# RFR24_AMS_Design_-_LTC6820_V1.net
KiCad netlist of a schematic drawn in Altium Designer
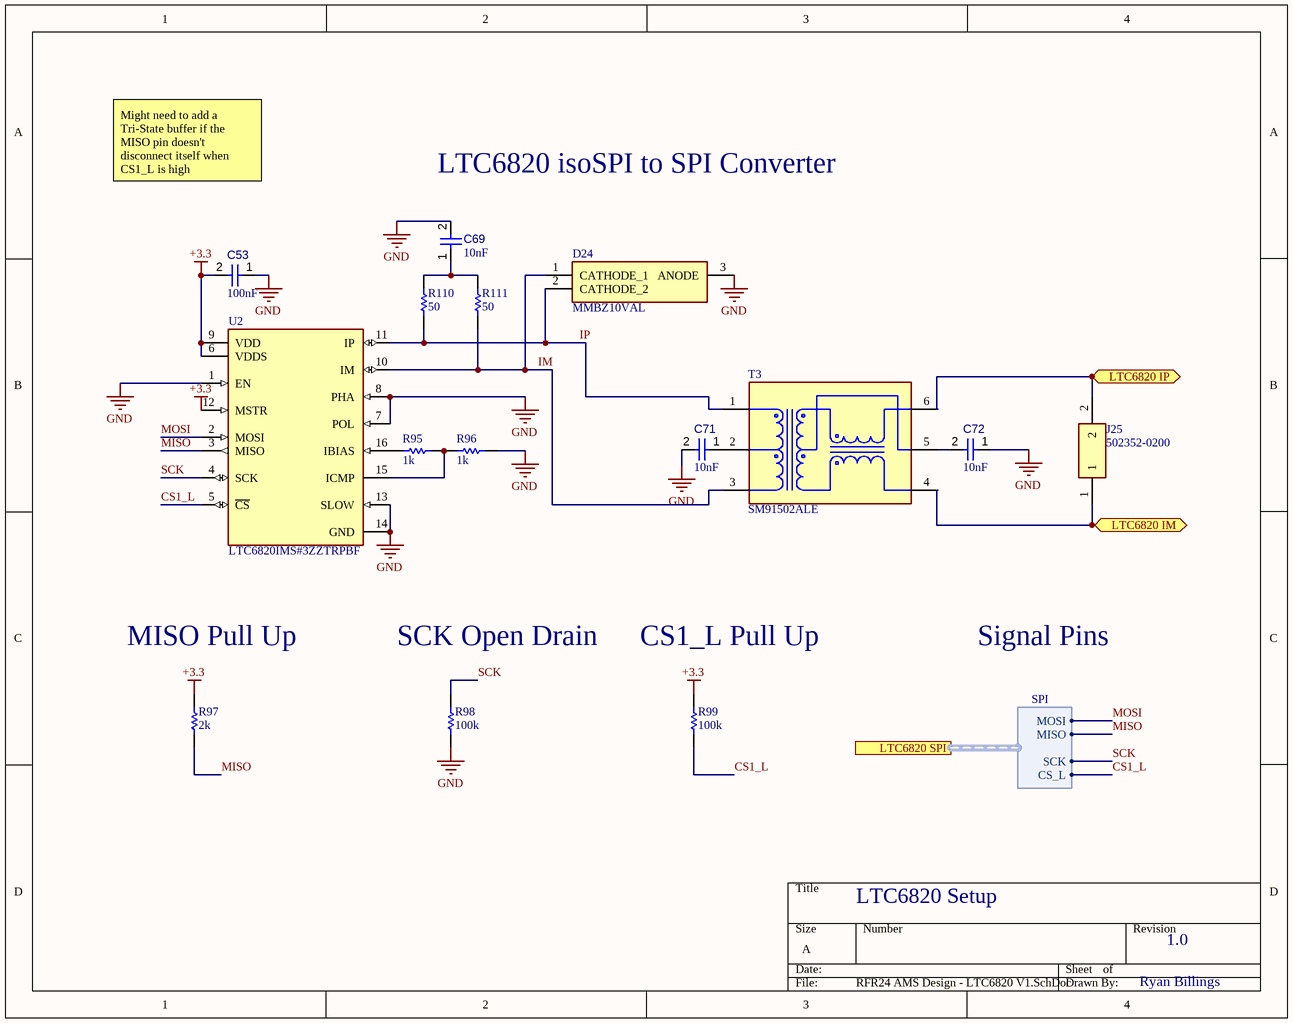
[diagram p0: RFR24 AMS Design - LTC6820 V1.SchDoc]

(export (version "E")
  (design (tool "Eeschema 10.0.6"))
  (components
    (comp (ref "C53")
      (value "100nF")
      (footprint "CAPC2013X145X50LL20T25")
      (description "Chip Capacitor, 1 uF, +/-10%, 25 V, 0805 (2012 Metric)")
      (fields (field (name "TOLERANCE") "10%") (field (name "Comment") "Capacitor 1 uF +/- 10% 25 V 0805"))
      (libsource (lib "Rutgers University") (part "CAP-NP-2"))
    )
    (comp (ref "C69")
      (value "10nF")
      (footprint "CAPC2013X145X50LL20T25")
      (description "Chip Capacitor, 1 uF, +/-10%, 25 V, 0805 (2012 Metric)")
      (fields (field (name "TOLERANCE") "10%") (field (name "Comment") "Capacitor 1 uF +/- 10% 25 V 0805"))
      (libsource (lib "Rutgers University") (part "CAP-NP-2"))
    )
    (comp (ref "C71")
      (value "10nF")
      (footprint "CAPC2013X145X50LL20T25")
      (description "Chip Capacitor, 1 uF, +/-10%, 25 V, 0805 (2012 Metric)")
      (fields (field (name "TOLERANCE") "10%") (field (name "Comment") "Capacitor 1 uF +/- 10% 25 V 0805"))
      (libsource (lib "Rutgers University") (part "CAP-NP-2"))
    )
    (comp (ref "C72")
      (value "10nF")
      (footprint "CAPC2013X145X50LL20T25")
      (description "Chip Capacitor, 1 uF, +/-10%, 25 V, 0805 (2012 Metric)")
      (fields (field (name "TOLERANCE") "10%") (field (name "Comment") "Capacitor 1 uF +/- 10% 25 V 0805"))
      (libsource (lib "Rutgers University") (part "CAP-NP-2"))
    )
    (comp (ref "D24")
      (value "MMBZ10VAL")
      (footprint "SamacSys:SOT95P230X110-3N")
      (description "TVS Diode (Uni-directional)")
      (libsource (lib "*") (part "MMBZ10VAL"))
    )
    (comp (ref "J25")
      (value "502352-0200")
      (footprint "SamacSys:5023520200")
      (description "Connector")
      (fields (field (name "MOUSER PART NUMBER") "538-502352-0200"))
      (libsource (lib "*") (part "502352-0200"))
    )
    (comp (ref "R95")
      (value "1k")
      (footprint "RESC2013X70X40LL20T20")
      (description "Chip Resistor, 1 KOhm, +/- 1%, 0.125 W, -55 to 155 degC, 0805 (2013 Metric)")
      (fields (field (name "TOLERANCE") "1%") (field (name "POWER") "125mW"))
      (libsource (lib "Rutgers University") (part "RES-2"))
    )
    (comp (ref "R96")
      (value "1k")
      (footprint "RESC2013X70X40LL20T20")
      (description "Chip Resistor, 1 KOhm, +/- 1%, 0.125 W, -55 to 155 degC, 0805 (2013 Metric)")
      (fields (field (name "TOLERANCE") "1%") (field (name "POWER") "125mW"))
      (libsource (lib "Rutgers University") (part "RES-2"))
    )
    (comp (ref "R97")
      (value "2k")
      (footprint "RESC2013X70X40LL20T20")
      (description "Chip Resistor, 1 KOhm, +/- 1%, 0.125 W, -55 to 155 degC, 0805 (2013 Metric)")
      (fields (field (name "TOLERANCE") "1%") (field (name "POWER") "125mW"))
      (libsource (lib "Rutgers University") (part "RES-2"))
    )
    (comp (ref "R98")
      (value "100k")
      (footprint "RESC2013X70X40LL20T20")
      (description "Chip Resistor, 1 KOhm, +/- 1%, 0.125 W, -55 to 155 degC, 0805 (2013 Metric)")
      (fields (field (name "TOLERANCE") "1%") (field (name "POWER") "125mW"))
      (libsource (lib "Rutgers University") (part "RES-2"))
    )
    (comp (ref "R99")
      (value "100k")
      (footprint "RESC2013X70X40LL20T20")
      (description "Chip Resistor, 1 KOhm, +/- 1%, 0.125 W, -55 to 155 degC, 0805 (2013 Metric)")
      (fields (field (name "TOLERANCE") "1%") (field (name "POWER") "125mW"))
      (libsource (lib "Rutgers University") (part "RES-2"))
    )
    (comp (ref "R110")
      (value "50")
      (footprint "RESC2013X70X40LL20T20")
      (description "Chip Resistor, 1 KOhm, +/- 1%, 0.125 W, -55 to 155 degC, 0805 (2013 Metric)")
      (fields (field (name "TOLERANCE") "1%") (field (name "POWER") "125mW"))
      (libsource (lib "Rutgers University") (part "RES-2"))
    )
    (comp (ref "R111")
      (value "50")
      (footprint "RESC2013X70X40LL20T20")
      (description "Chip Resistor, 1 KOhm, +/- 1%, 0.125 W, -55 to 155 degC, 0805 (2013 Metric)")
      (fields (field (name "TOLERANCE") "1%") (field (name "POWER") "125mW"))
      (libsource (lib "Rutgers University") (part "RES-2"))
    )
    (comp (ref "T3")
      (value "SM91502ALE")
      (footprint "FP-SM91502ALE-MFG")
      (description "BMS XFORMER 1-CH 1000V AECQ +125")
      (fields
        (field (name "MANUFACTURER") "Bourns")
        (field (name "OCTOPART") "https://octopart.com/sm91502ale-bourns-95732123")
      )
      (libsource (lib "Altium Content Vault") (part "554ff5199021d68917f526d8699f58a"))
    )
    (comp (ref "U2")
      (value "LTC6820IMS#3ZZTRPBF")
      (footprint "FP-MS-16-05-08-1669-IPC_C")
      (description "IC INTERFACE SPECIALIZED 16MSOP")
      (libsource (lib "Altium Content Vault") (part "435d8f2fce35f3197db5f67e0dab696"))
    )
  )
  (nets
    (net (code "2") (name "+3.3") (class "Default")
      (node (ref "C53") (pin "2") (pinfunction "2_2") (pintype "passive"))
      (node (ref "R97") (pin "2") (pinfunction "2_2") (pintype "passive"))
      (node (ref "R99") (pin "2") (pinfunction "2_2") (pintype "passive"))
      (node (ref "U2") (pin "12") (pinfunction "MSTR_12") (pintype "input"))
      (node (ref "U2") (pin "6") (pinfunction "VDDS_6") (pintype "power_in"))
      (node (ref "U2") (pin "9") (pinfunction "VDD_9") (pintype "power_in"))
    )
    (net (code "3") (name "/CS1_L") (class "Default")
      (node (ref "R99") (pin "1") (pinfunction "1_1") (pintype "passive"))
      (node (ref "U2") (pin "5") (pinfunction "~{CS}_5") (pintype "bidirectional"))
    )
    (net (code "4") (name "/IM") (class "Default")
      (node (ref "D24") (pin "1") (pinfunction "CATHODE_1_1") (pintype "passive"))
      (node (ref "R111") (pin "1") (pinfunction "1_1") (pintype "passive"))
      (node (ref "T3") (pin "3") (pinfunction "3_3") (pintype "passive"))
      (node (ref "U2") (pin "10") (pinfunction "IM_10") (pintype "bidirectional"))
    )
    (net (code "5") (name "/IP") (class "Default")
      (node (ref "D24") (pin "2") (pinfunction "CATHODE_2_2") (pintype "passive"))
      (node (ref "R110") (pin "1") (pinfunction "1_1") (pintype "passive"))
      (node (ref "T3") (pin "1") (pinfunction "1_1") (pintype "passive"))
      (node (ref "U2") (pin "11") (pinfunction "IP_11") (pintype "bidirectional"))
    )
    (net (code "6") (name "/LTC6820 IM") (class "Default")
      (node (ref "J25") (pin "1") (pinfunction "1_1") (pintype "passive"))
      (node (ref "T3") (pin "4") (pinfunction "4_4") (pintype "passive"))
    )
    (net (code "7") (name "/LTC6820 IP") (class "Default")
      (node (ref "J25") (pin "2") (pinfunction "2_2") (pintype "passive"))
      (node (ref "T3") (pin "6") (pinfunction "6_6") (pintype "passive"))
    )
    (net (code "8") (name "/MISO") (class "Default")
      (node (ref "R97") (pin "1") (pinfunction "1_1") (pintype "passive"))
      (node (ref "U2") (pin "3") (pinfunction "MISO_3") (pintype "output"))
    )
    (net (code "9") (name "/MOSI") (class "Default")
      (node (ref "U2") (pin "2") (pinfunction "MOSI_2") (pintype "input"))
    )
    (net (code "10") (name "/SCK") (class "Default")
      (node (ref "R98") (pin "2") (pinfunction "2_2") (pintype "passive"))
      (node (ref "U2") (pin "4") (pinfunction "SCK_4") (pintype "bidirectional"))
    )
    (net (code "12") (name "GND") (class "Default")
      (node (ref "C53") (pin "1") (pinfunction "1_1") (pintype "passive"))
      (node (ref "C69") (pin "2") (pinfunction "2_2") (pintype "passive"))
      (node (ref "C71") (pin "2") (pinfunction "2_2") (pintype "passive"))
      (node (ref "C72") (pin "1") (pinfunction "1_1") (pintype "passive"))
      (node (ref "D24") (pin "3") (pinfunction "ANODE_3") (pintype "passive"))
      (node (ref "R96") (pin "2") (pinfunction "2_2") (pintype "passive"))
      (node (ref "R98") (pin "1") (pinfunction "1_1") (pintype "passive"))
      (node (ref "U2") (pin "1") (pinfunction "EN_1") (pintype "input"))
      (node (ref "U2") (pin "13") (pinfunction "SLOW_13") (pintype "input"))
      (node (ref "U2") (pin "14") (pinfunction "GND_14") (pintype "power_in"))
      (node (ref "U2") (pin "7") (pinfunction "POL_7") (pintype "input"))
      (node (ref "U2") (pin "8") (pinfunction "PHA_8") (pintype "input"))
    )
    (net (code "13") (name "Net-(C69-Pad1)") (class "Default")
      (node (ref "C69") (pin "1") (pinfunction "1_1") (pintype "passive"))
      (node (ref "R110") (pin "2") (pinfunction "2_2") (pintype "passive"))
      (node (ref "R111") (pin "2") (pinfunction "2_2") (pintype "passive"))
    )
    (net (code "14") (name "Net-(C71-Pad1)") (class "Default")
      (node (ref "C71") (pin "1") (pinfunction "1_1") (pintype "passive"))
      (node (ref "T3") (pin "2") (pinfunction "2_2") (pintype "passive"))
    )
    (net (code "15") (name "Net-(C72-Pad2)") (class "Default")
      (node (ref "C72") (pin "2") (pinfunction "2_2") (pintype "passive"))
      (node (ref "T3") (pin "5") (pinfunction "5_5") (pintype "passive"))
    )
    (net (code "16") (name "Net-(U2-IBIAS)") (class "Default")
      (node (ref "R95") (pin "1") (pinfunction "1_1") (pintype "passive"))
      (node (ref "U2") (pin "16") (pinfunction "IBIAS_16") (pintype "input"))
    )
    (net (code "17") (name "Net-(U2-ICMP)") (class "Default")
      (node (ref "R95") (pin "2") (pinfunction "2_2") (pintype "passive"))
      (node (ref "R96") (pin "1") (pinfunction "1_1") (pintype "passive"))
      (node (ref "U2") (pin "15") (pinfunction "ICMP_15") (pintype "passive"))
    )
  )
)
